# PIC.net
KiCad netlist of a schematic drawn in Altium Designer
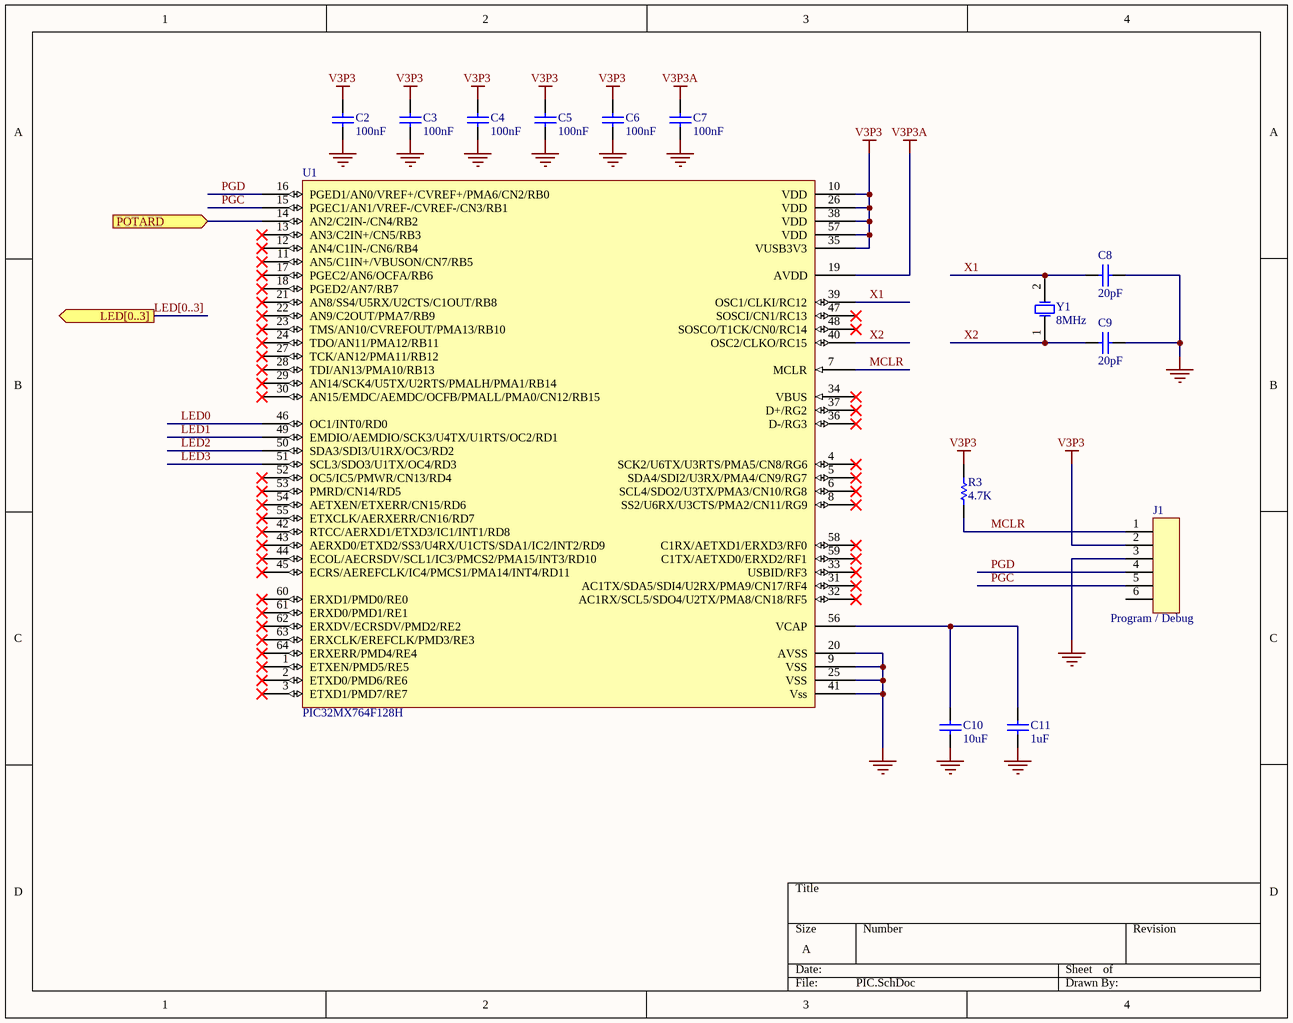
[diagram p0: PIC.SchDoc]

(export (version "E")
  (design (tool "Eeschema 10.0.6"))
  (components
    (comp (ref "C2")
      (value "100nF")
      (footprint "CAPC1608N")
      (description "Capacitor")
      (fields (field (name "PUBLISHER") "Altium Limited"))
      (libsource (lib "Miscellaneous Devices") (part "Cap"))
    )
    (comp (ref "C3")
      (value "100nF")
      (footprint "CAPC1608N")
      (description "Capacitor")
      (fields (field (name "PUBLISHER") "Altium Limited"))
      (libsource (lib "Miscellaneous Devices") (part "Cap"))
    )
    (comp (ref "C4")
      (value "100nF")
      (footprint "CAPC1608N")
      (description "Capacitor")
      (fields (field (name "PUBLISHER") "Altium Limited"))
      (libsource (lib "Miscellaneous Devices") (part "Cap"))
    )
    (comp (ref "C5")
      (value "100nF")
      (footprint "CAPC1608N")
      (description "Capacitor")
      (fields (field (name "PUBLISHER") "Altium Limited"))
      (libsource (lib "Miscellaneous Devices") (part "Cap"))
    )
    (comp (ref "C6")
      (value "100nF")
      (footprint "CAPC1608N")
      (description "Capacitor")
      (fields (field (name "PUBLISHER") "Altium Limited"))
      (libsource (lib "Miscellaneous Devices") (part "Cap"))
    )
    (comp (ref "C7")
      (value "100nF")
      (footprint "CAPC1608N")
      (description "Capacitor")
      (fields (field (name "PUBLISHER") "Altium Limited"))
      (libsource (lib "Miscellaneous Devices") (part "Cap"))
    )
    (comp (ref "C8")
      (value "20pF")
      (footprint "CAPC1608N")
      (description "Capacitor")
      (fields (field (name "PUBLISHER") "Altium Limited"))
      (libsource (lib "Miscellaneous Devices") (part "Cap"))
    )
    (comp (ref "C9")
      (value "20pF")
      (footprint "CAPC1608N")
      (description "Capacitor")
      (fields (field (name "PUBLISHER") "Altium Limited"))
      (libsource (lib "Miscellaneous Devices") (part "Cap"))
    )
    (comp (ref "C10")
      (value "10uF")
      (footprint "CAPC2012N")
      (description "Capacitor")
      (fields (field (name "PUBLISHER") "Altium Limited"))
      (libsource (lib "Miscellaneous Devices") (part "Cap"))
    )
    (comp (ref "C11")
      (value "1uF")
      (footprint "CAPC1608N")
      (description "Capacitor")
      (fields (field (name "PUBLISHER") "Altium Limited"))
      (libsource (lib "Miscellaneous Devices") (part "Cap"))
    )
    (comp (ref "J1")
      (value "Program / Debug")
      (footprint "RJ12_90")
      (libsource (lib "Proram_debug") (part "Component_1"))
    )
    (comp (ref "R3")
      (value "4.7K")
      (footprint "RESC1608N")
      (description "Resistor")
      (fields (field (name "PUBLISHER") "Altium Limited"))
      (libsource (lib "Miscellaneous Devices") (part "Res1"))
    )
    (comp (ref "U1")
      (value "PIC32MX764F128H")
      (footprint "QFP50P1200X1200X120-64")
      (libsource (lib "TP2") (part "PIC32MX764F128H"))
    )
    (comp (ref "Y1")
      (value "8MHz")
      (footprint "XTAL139X50X45")
      (description "Crystal Oscillator")
      (fields (field (name "PUBLISHER") "Altium Limited"))
      (libsource (lib "Miscellaneous Devices") (part "XTAL"))
    )
  )
  (nets
    (net (code "1") (name "/LED0") (class "Default")
      (node (ref "U1") (pin "46") (pinfunction "OC1/INT0/RD0_46") (pintype "bidirectional"))
    )
    (net (code "2") (name "/LED1") (class "Default")
      (node (ref "U1") (pin "49") (pinfunction "EMDIO/AEMDIO/SCK3/U4TX/U1RTS/OC2/RD1_49") (pintype "bidirectional"))
    )
    (net (code "3") (name "/LED2") (class "Default")
      (node (ref "U1") (pin "50") (pinfunction "SDA3/SDI3/U1RX/OC3/RD2_50") (pintype "bidirectional"))
    )
    (net (code "4") (name "/LED3") (class "Default")
      (node (ref "U1") (pin "51") (pinfunction "SCL3/SDO3/U1TX/OC4/RD3_51") (pintype "bidirectional"))
    )
    (net (code "6") (name "/MCLR") (class "Default")
      (node (ref "J1") (pin "1") (pinfunction "1_1") (pintype "passive"))
      (node (ref "R3") (pin "1") (pinfunction "1_1") (pintype "passive"))
      (node (ref "U1") (pin "7") (pinfunction "MCLR_7") (pintype "input"))
    )
    (net (code "7") (name "/PGC") (class "Default")
      (node (ref "J1") (pin "5") (pinfunction "5_5") (pintype "passive"))
      (node (ref "U1") (pin "15") (pinfunction "PGEC1/AN1/VREF-/CVREF-/CN3/RB1_15") (pintype "bidirectional"))
    )
    (net (code "8") (name "/PGD") (class "Default")
      (node (ref "J1") (pin "4") (pinfunction "4_4") (pintype "passive"))
      (node (ref "U1") (pin "16") (pinfunction "PGED1/AN0/VREF+/CVREF+/PMA6/CN2/RB0_16") (pintype "bidirectional"))
    )
    (net (code "9") (name "/POTARD") (class "Default")
      (node (ref "U1") (pin "14") (pinfunction "AN2/C2IN-/CN4/RB2_14") (pintype "bidirectional"))
    )
    (net (code "10") (name "/X1") (class "Default")
      (node (ref "C8") (pin "2") (pinfunction "2_2") (pintype "passive"))
      (node (ref "U1") (pin "39") (pinfunction "OSC1/CLKI/RC12_39") (pintype "bidirectional"))
      (node (ref "Y1") (pin "2") (pinfunction "OSC2_2") (pintype "passive"))
    )
    (net (code "11") (name "/X2") (class "Default")
      (node (ref "C9") (pin "2") (pinfunction "2_2") (pintype "passive"))
      (node (ref "U1") (pin "40") (pinfunction "OSC2/CLKO/RC15_40") (pintype "bidirectional"))
      (node (ref "Y1") (pin "1") (pinfunction "OSC1_1") (pintype "passive"))
    )
    (net (code "12") (name "GND") (class "Default")
      (node (ref "C10") (pin "1") (pinfunction "1_1") (pintype "passive"))
      (node (ref "C11") (pin "1") (pinfunction "1_1") (pintype "passive"))
      (node (ref "C2") (pin "1") (pinfunction "1_1") (pintype "passive"))
      (node (ref "C3") (pin "1") (pinfunction "1_1") (pintype "passive"))
      (node (ref "C4") (pin "1") (pinfunction "1_1") (pintype "passive"))
      (node (ref "C5") (pin "1") (pinfunction "1_1") (pintype "passive"))
      (node (ref "C6") (pin "1") (pinfunction "1_1") (pintype "passive"))
      (node (ref "C7") (pin "1") (pinfunction "1_1") (pintype "passive"))
      (node (ref "C8") (pin "1") (pinfunction "1_1") (pintype "passive"))
      (node (ref "C9") (pin "1") (pinfunction "1_1") (pintype "passive"))
      (node (ref "J1") (pin "3") (pinfunction "3_3") (pintype "passive"))
      (node (ref "U1") (pin "20") (pinfunction "AVSS_20") (pintype "passive"))
      (node (ref "U1") (pin "25") (pinfunction "VSS_25") (pintype "passive"))
      (node (ref "U1") (pin "41") (pinfunction "Vss_41") (pintype "passive"))
      (node (ref "U1") (pin "9") (pinfunction "VSS_9") (pintype "passive"))
    )
    (net (code "13") (name "Net-(U1-VCAP)") (class "Default")
      (node (ref "C10") (pin "2") (pinfunction "2_2") (pintype "passive"))
      (node (ref "C11") (pin "2") (pinfunction "2_2") (pintype "passive"))
      (node (ref "U1") (pin "56") (pinfunction "VCAP_56") (pintype "passive"))
    )
    (net (code "14") (name "V3P3") (class "Default")
      (node (ref "C2") (pin "2") (pinfunction "2_2") (pintype "passive"))
      (node (ref "C3") (pin "2") (pinfunction "2_2") (pintype "passive"))
      (node (ref "C4") (pin "2") (pinfunction "2_2") (pintype "passive"))
      (node (ref "C5") (pin "2") (pinfunction "2_2") (pintype "passive"))
      (node (ref "C6") (pin "2") (pinfunction "2_2") (pintype "passive"))
      (node (ref "J1") (pin "2") (pinfunction "2_2") (pintype "passive"))
      (node (ref "R3") (pin "2") (pinfunction "2_2") (pintype "passive"))
      (node (ref "U1") (pin "10") (pinfunction "VDD_10") (pintype "passive"))
      (node (ref "U1") (pin "26") (pinfunction "VDD_26") (pintype "passive"))
      (node (ref "U1") (pin "35") (pinfunction "VUSB3V3_35") (pintype "passive"))
      (node (ref "U1") (pin "38") (pinfunction "VDD_38") (pintype "passive"))
      (node (ref "U1") (pin "57") (pinfunction "VDD_57") (pintype "passive"))
    )
    (net (code "15") (name "V3P3A") (class "Default")
      (node (ref "C7") (pin "2") (pinfunction "2_2") (pintype "passive"))
      (node (ref "U1") (pin "19") (pinfunction "AVDD_19") (pintype "passive"))
    )
    (net (code "16") (name "unconnected-(J1-Pad6)") (class "Default")
      (node (ref "J1") (pin "6") (pinfunction "6_6") (pintype "passive"))
    )
    (net (code "17") (name "unconnected-(U1-AC1RX{slash}SCL5{slash}SDO4{slash}U2TX{slash}PMA8{slash}CN18{slash}RF5-Pad32)") (class "Default")
      (node (ref "U1") (pin "32") (pinfunction "AC1RX/SCL5/SDO4/U2TX/PMA8/CN18/RF5_32") (pintype "bidirectional+no_connect"))
    )
    (net (code "18") (name "unconnected-(U1-AC1TX{slash}SDA5{slash}SDI4{slash}U2RX{slash}PMA9{slash}CN17{slash}RF4-Pad31)") (class "Default")
      (node (ref "U1") (pin "31") (pinfunction "AC1TX/SDA5/SDI4/U2RX/PMA9/CN17/RF4_31") (pintype "bidirectional+no_connect"))
    )
    (net (code "19") (name "unconnected-(U1-AERXD0{slash}ETXD2{slash}SS3{slash}U4RX{slash}U1CTS{slash}SDA1{slash}IC2{slash}INT2{slash}RD9-Pad43)") (class "Default")
      (node (ref "U1") (pin "43") (pinfunction "AERXD0/ETXD2/SS3/U4RX/U1CTS/SDA1/IC2/INT2/RD9_43") (pintype "bidirectional+no_connect"))
    )
    (net (code "20") (name "unconnected-(U1-AETXEN{slash}ETXERR{slash}CN15{slash}RD6-Pad54)") (class "Default")
      (node (ref "U1") (pin "54") (pinfunction "AETXEN/ETXERR/CN15/RD6_54") (pintype "bidirectional+no_connect"))
    )
    (net (code "21") (name "unconnected-(U1-AN3{slash}C2IN+{slash}CN5{slash}RB3-Pad13)") (class "Default")
      (node (ref "U1") (pin "13") (pinfunction "AN3/C2IN+/CN5/RB3_13") (pintype "bidirectional+no_connect"))
    )
    (net (code "22") (name "unconnected-(U1-AN4{slash}C1IN-{slash}CN6{slash}RB4-Pad12)") (class "Default")
      (node (ref "U1") (pin "12") (pinfunction "AN4/C1IN-/CN6/RB4_12") (pintype "bidirectional+no_connect"))
    )
    (net (code "23") (name "unconnected-(U1-AN5{slash}C1IN+{slash}VBUSON{slash}CN7{slash}RB5-Pad11)") (class "Default")
      (node (ref "U1") (pin "11") (pinfunction "AN5/C1IN+/VBUSON/CN7/RB5_11") (pintype "bidirectional+no_connect"))
    )
    (net (code "24") (name "unconnected-(U1-AN8{slash}SS4{slash}U5RX{slash}U2CTS{slash}C1OUT{slash}RB8-Pad21)") (class "Default")
      (node (ref "U1") (pin "21") (pinfunction "AN8/SS4/U5RX/U2CTS/C1OUT/RB8_21") (pintype "bidirectional+no_connect"))
    )
    (net (code "25") (name "unconnected-(U1-AN9{slash}C2OUT{slash}PMA7{slash}RB9-Pad22)") (class "Default")
      (node (ref "U1") (pin "22") (pinfunction "AN9/C2OUT/PMA7/RB9_22") (pintype "bidirectional+no_connect"))
    )
    (net (code "26") (name "unconnected-(U1-AN14{slash}SCK4{slash}U5TX{slash}U2RTS{slash}PMALH{slash}PMA1{slash}RB14-Pad29)") (class "Default")
      (node (ref "U1") (pin "29") (pinfunction "AN14/SCK4/U5TX/U2RTS/PMALH/PMA1/RB14_29") (pintype "bidirectional+no_connect"))
    )
    (net (code "27") (name "unconnected-(U1-AN15{slash}EMDC{slash}AEMDC{slash}OCFB{slash}PMALL{slash}PMA0{slash}CN12{slash}RB15-Pad30)") (class "Default")
      (node (ref "U1") (pin "30") (pinfunction "AN15/EMDC/AEMDC/OCFB/PMALL/PMA0/CN12/RB15_30") (pintype "bidirectional+no_connect"))
    )
    (net (code "28") (name "unconnected-(U1-C1RX{slash}AETXD1{slash}ERXD3{slash}RF0-Pad58)") (class "Default")
      (node (ref "U1") (pin "58") (pinfunction "C1RX/AETXD1/ERXD3/RF0_58") (pintype "bidirectional+no_connect"))
    )
    (net (code "29") (name "unconnected-(U1-C1TX{slash}AETXD0{slash}ERXD2{slash}RF1-Pad59)") (class "Default")
      (node (ref "U1") (pin "59") (pinfunction "C1TX/AETXD0/ERXD2/RF1_59") (pintype "bidirectional+no_connect"))
    )
    (net (code "30") (name "unconnected-(U1-D+{slash}RG2-Pad37)") (class "Default")
      (node (ref "U1") (pin "37") (pinfunction "D+/RG2_37") (pintype "bidirectional+no_connect"))
    )
    (net (code "31") (name "unconnected-(U1-D-{slash}RG3-Pad36)") (class "Default")
      (node (ref "U1") (pin "36") (pinfunction "D-/RG3_36") (pintype "bidirectional+no_connect"))
    )
    (net (code "32") (name "unconnected-(U1-ECOL{slash}AECRSDV{slash}SCL1{slash}IC3{slash}PMCS2{slash}PMA15{slash}INT3{slash}RD10-Pad44)") (class "Default")
      (node (ref "U1") (pin "44") (pinfunction "ECOL/AECRSDV/SCL1/IC3/PMCS2/PMA15/INT3/RD10_44") (pintype "bidirectional+no_connect"))
    )
    (net (code "33") (name "unconnected-(U1-ECRS{slash}AEREFCLK{slash}IC4{slash}PMCS1{slash}PMA14{slash}INT4{slash}RD11-Pad45)") (class "Default")
      (node (ref "U1") (pin "45") (pinfunction "ECRS/AEREFCLK/IC4/PMCS1/PMA14/INT4/RD11_45") (pintype "bidirectional+no_connect"))
    )
    (net (code "34") (name "unconnected-(U1-ERXCLK{slash}EREFCLK{slash}PMD3{slash}RE3-Pad63)") (class "Default")
      (node (ref "U1") (pin "63") (pinfunction "ERXCLK/EREFCLK/PMD3/RE3_63") (pintype "bidirectional+no_connect"))
    )
    (net (code "35") (name "unconnected-(U1-ERXD0{slash}PMD1{slash}RE1-Pad61)") (class "Default")
      (node (ref "U1") (pin "61") (pinfunction "ERXD0/PMD1/RE1_61") (pintype "bidirectional+no_connect"))
    )
    (net (code "36") (name "unconnected-(U1-ERXD1{slash}PMD0{slash}RE0-Pad60)") (class "Default")
      (node (ref "U1") (pin "60") (pinfunction "ERXD1/PMD0/RE0_60") (pintype "bidirectional+no_connect"))
    )
    (net (code "37") (name "unconnected-(U1-ERXDV{slash}ECRSDV{slash}PMD2{slash}RE2-Pad62)") (class "Default")
      (node (ref "U1") (pin "62") (pinfunction "ERXDV/ECRSDV/PMD2/RE2_62") (pintype "bidirectional+no_connect"))
    )
    (net (code "38") (name "unconnected-(U1-ERXERR{slash}PMD4{slash}RE4-Pad64)") (class "Default")
      (node (ref "U1") (pin "64") (pinfunction "ERXERR/PMD4/RE4_64") (pintype "bidirectional+no_connect"))
    )
    (net (code "39") (name "unconnected-(U1-ETXCLK{slash}AERXERR{slash}CN16{slash}RD7-Pad55)") (class "Default")
      (node (ref "U1") (pin "55") (pinfunction "ETXCLK/AERXERR/CN16/RD7_55") (pintype "bidirectional+no_connect"))
    )
    (net (code "40") (name "unconnected-(U1-ETXD0{slash}PMD6{slash}RE6-Pad2)") (class "Default")
      (node (ref "U1") (pin "2") (pinfunction "ETXD0/PMD6/RE6_2") (pintype "bidirectional+no_connect"))
    )
    (net (code "41") (name "unconnected-(U1-ETXD1{slash}PMD7{slash}RE7-Pad3)") (class "Default")
      (node (ref "U1") (pin "3") (pinfunction "ETXD1/PMD7/RE7_3") (pintype "bidirectional+no_connect"))
    )
    (net (code "42") (name "unconnected-(U1-ETXEN{slash}PMD5{slash}RE5-Pad1)") (class "Default")
      (node (ref "U1") (pin "1") (pinfunction "ETXEN/PMD5/RE5_1") (pintype "bidirectional+no_connect"))
    )
    (net (code "43") (name "unconnected-(U1-OC5{slash}IC5{slash}PMWR{slash}CN13{slash}RD4-Pad52)") (class "Default")
      (node (ref "U1") (pin "52") (pinfunction "OC5/IC5/PMWR/CN13/RD4_52") (pintype "bidirectional+no_connect"))
    )
    (net (code "44") (name "unconnected-(U1-PGEC2{slash}AN6{slash}OCFA{slash}RB6-Pad17)") (class "Default")
      (node (ref "U1") (pin "17") (pinfunction "PGEC2/AN6/OCFA/RB6_17") (pintype "bidirectional+no_connect"))
    )
    (net (code "45") (name "unconnected-(U1-PGED2{slash}AN7{slash}RB7-Pad18)") (class "Default")
      (node (ref "U1") (pin "18") (pinfunction "PGED2/AN7/RB7_18") (pintype "bidirectional+no_connect"))
    )
    (net (code "46") (name "unconnected-(U1-PMRD{slash}CN14{slash}RD5-Pad53)") (class "Default")
      (node (ref "U1") (pin "53") (pinfunction "PMRD/CN14/RD5_53") (pintype "bidirectional+no_connect"))
    )
    (net (code "47") (name "unconnected-(U1-RTCC{slash}AERXD1{slash}ETXD3{slash}IC1{slash}INT1{slash}RD8-Pad42)") (class "Default")
      (node (ref "U1") (pin "42") (pinfunction "RTCC/AERXD1/ETXD3/IC1/INT1/RD8_42") (pintype "bidirectional+no_connect"))
    )
    (net (code "48") (name "unconnected-(U1-SCK2{slash}U6TX{slash}U3RTS{slash}PMA5{slash}CN8{slash}RG6-Pad4)") (class "Default")
      (node (ref "U1") (pin "4") (pinfunction "SCK2/U6TX/U3RTS/PMA5/CN8/RG6_4") (pintype "bidirectional+no_connect"))
    )
    (net (code "49") (name "unconnected-(U1-SCL4{slash}SDO2{slash}U3TX{slash}PMA3{slash}CN10{slash}RG8-Pad6)") (class "Default")
      (node (ref "U1") (pin "6") (pinfunction "SCL4/SDO2/U3TX/PMA3/CN10/RG8_6") (pintype "bidirectional+no_connect"))
    )
    (net (code "50") (name "unconnected-(U1-SDA4{slash}SDI2{slash}U3RX{slash}PMA4{slash}CN9{slash}RG7-Pad5)") (class "Default")
      (node (ref "U1") (pin "5") (pinfunction "SDA4/SDI2/U3RX/PMA4/CN9/RG7_5") (pintype "bidirectional+no_connect"))
    )
    (net (code "51") (name "unconnected-(U1-SOSCI{slash}CN1{slash}RC13-Pad47)") (class "Default")
      (node (ref "U1") (pin "47") (pinfunction "SOSCI/CN1/RC13_47") (pintype "bidirectional+no_connect"))
    )
    (net (code "52") (name "unconnected-(U1-SOSCO{slash}T1CK{slash}CN0{slash}RC14-Pad48)") (class "Default")
      (node (ref "U1") (pin "48") (pinfunction "SOSCO/T1CK/CN0/RC14_48") (pintype "bidirectional+no_connect"))
    )
    (net (code "53") (name "unconnected-(U1-SS2{slash}U6RX{slash}U3CTS{slash}PMA2{slash}CN11{slash}RG9-Pad8)") (class "Default")
      (node (ref "U1") (pin "8") (pinfunction "SS2/U6RX/U3CTS/PMA2/CN11/RG9_8") (pintype "bidirectional+no_connect"))
    )
    (net (code "54") (name "unconnected-(U1-TCK{slash}AN12{slash}PMA11{slash}RB12-Pad27)") (class "Default")
      (node (ref "U1") (pin "27") (pinfunction "TCK/AN12/PMA11/RB12_27") (pintype "bidirectional+no_connect"))
    )
    (net (code "55") (name "unconnected-(U1-TDI{slash}AN13{slash}PMA10{slash}RB13-Pad28)") (class "Default")
      (node (ref "U1") (pin "28") (pinfunction "TDI/AN13/PMA10/RB13_28") (pintype "bidirectional+no_connect"))
    )
    (net (code "56") (name "unconnected-(U1-TDO{slash}AN11{slash}PMA12{slash}RB11-Pad24)") (class "Default")
      (node (ref "U1") (pin "24") (pinfunction "TDO/AN11/PMA12/RB11_24") (pintype "bidirectional+no_connect"))
    )
    (net (code "57") (name "unconnected-(U1-TMS{slash}AN10{slash}CVREFOUT{slash}PMA13{slash}RB10-Pad23)") (class "Default")
      (node (ref "U1") (pin "23") (pinfunction "TMS/AN10/CVREFOUT/PMA13/RB10_23") (pintype "bidirectional+no_connect"))
    )
    (net (code "58") (name "unconnected-(U1-USBID{slash}RF3-Pad33)") (class "Default")
      (node (ref "U1") (pin "33") (pinfunction "USBID/RF3_33") (pintype "bidirectional+no_connect"))
    )
    (net (code "59") (name "unconnected-(U1-VBUS-Pad34)") (class "Default")
      (node (ref "U1") (pin "34") (pinfunction "VBUS_34") (pintype "input+no_connect"))
    )
  )
)
